# SandeepEtchASketch.net
KiCad netlist of a schematic drawn in EAGLE
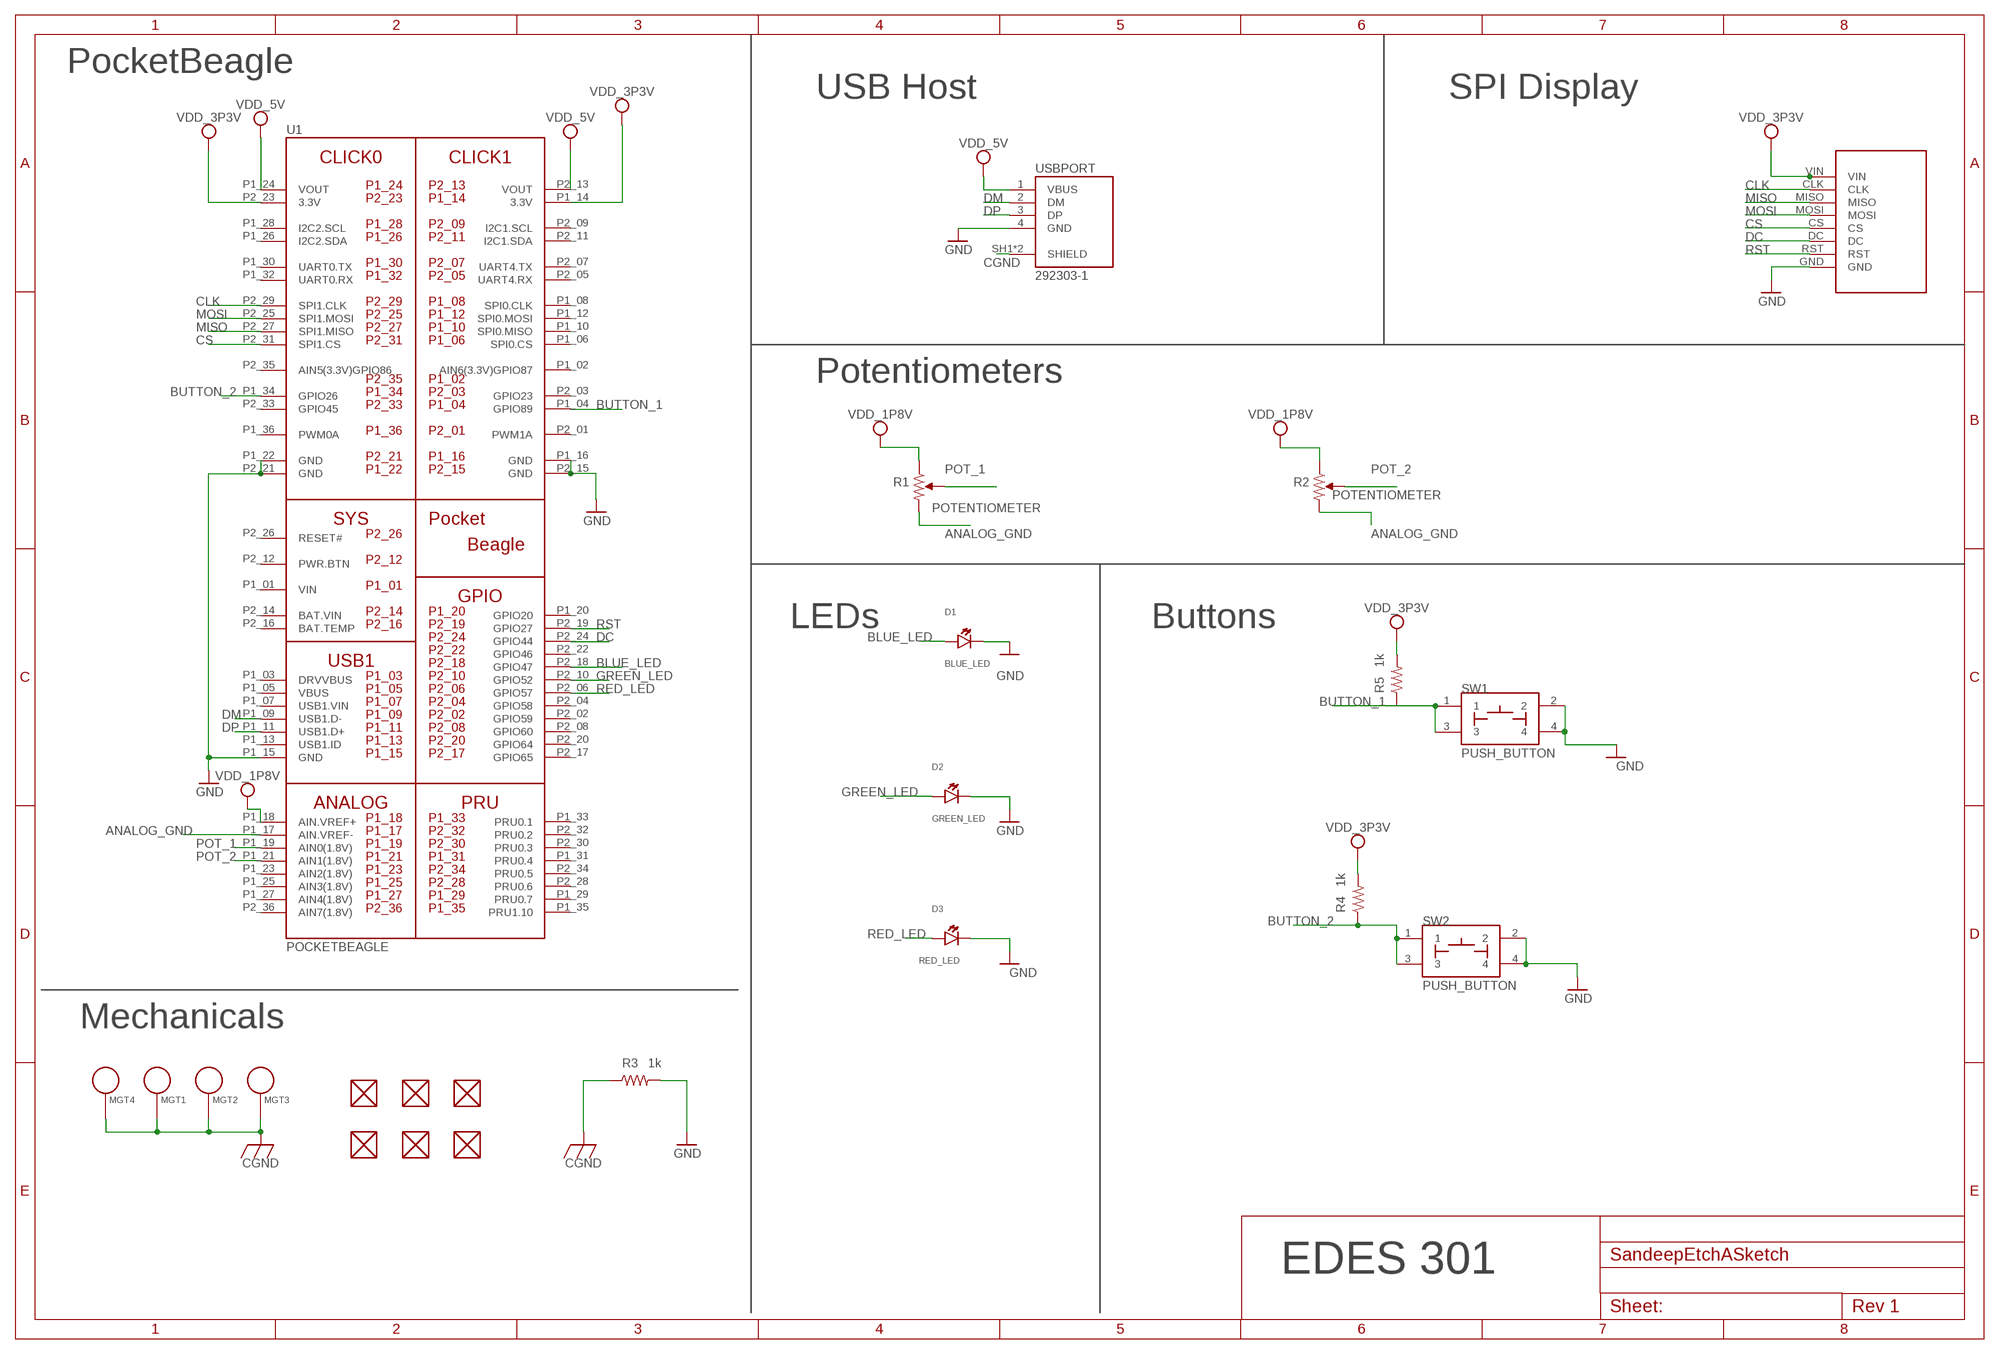
[diagram p0: schematic, sheet 1]

(export (version "E")
  (design (tool "Eeschema 10.0.6"))
  (components
    (comp (ref "D1")
      (value "BLUE_LED")
      (footprint "eagle-import:EIA-STD")
      (libsource (lib "eagle-import") (part "LED"))
    )
    (comp (ref "D2")
      (value "GREEN_LED")
      (footprint "eagle-import:EIA-STD")
      (libsource (lib "eagle-import") (part "LED"))
    )
    (comp (ref "D3")
      (value "RED_LED")
      (footprint "eagle-import:EIA-STD")
      (libsource (lib "eagle-import") (part "LED"))
    )
    (comp (ref "FUD1")
      (value "FIDUCIAL")
      (footprint "eagle-import:FIDUCIAL_40MIL")
      (libsource (lib "eagle-import") (part "FIDUCIAL"))
    )
    (comp (ref "FUD2")
      (value "FIDUCIAL")
      (footprint "eagle-import:FIDUCIAL_40MIL")
      (libsource (lib "eagle-import") (part "FIDUCIAL"))
    )
    (comp (ref "FUD3")
      (value "FIDUCIAL")
      (footprint "eagle-import:FIDUCIAL_40MIL")
      (libsource (lib "eagle-import") (part "FIDUCIAL"))
    )
    (comp (ref "FUD4")
      (value "FIDUCIAL")
      (footprint "eagle-import:FIDUCIAL_40MIL")
      (libsource (lib "eagle-import") (part "FIDUCIAL"))
    )
    (comp (ref "FUD5")
      (value "FIDUCIAL")
      (footprint "eagle-import:FIDUCIAL_40MIL")
      (libsource (lib "eagle-import") (part "FIDUCIAL"))
    )
    (comp (ref "FUD6")
      (value "FIDUCIAL")
      (footprint "eagle-import:FIDUCIAL_40MIL")
      (libsource (lib "eagle-import") (part "FIDUCIAL"))
    )
    (comp (ref "MGT1")
      (value "MOUNTING_HOLE")
      (footprint "eagle-import:MOUNTING_HOLE")
      (libsource (lib "eagle-import") (part "MOUNTING_HOLE"))
    )
    (comp (ref "MGT2")
      (value "MOUNTING_HOLE")
      (footprint "eagle-import:MOUNTING_HOLE")
      (libsource (lib "eagle-import") (part "MOUNTING_HOLE"))
    )
    (comp (ref "MGT3")
      (value "MOUNTING_HOLE")
      (footprint "eagle-import:MOUNTING_HOLE")
      (libsource (lib "eagle-import") (part "MOUNTING_HOLE"))
    )
    (comp (ref "MGT4")
      (value "MOUNTING_HOLE")
      (footprint "eagle-import:MOUNTING_HOLE")
      (libsource (lib "eagle-import") (part "MOUNTING_HOLE"))
    )
    (comp (ref "R1")
      (value "POTENTIOMETER")
      (footprint "eagle-import:POT-PO90S")
      (libsource (lib "eagle-import") (part "POTENTIOMETER"))
    )
    (comp (ref "R2")
      (value "POTENTIOMETER")
      (footprint "eagle-import:POT-PO90S")
      (libsource (lib "eagle-import") (part "POTENTIOMETER"))
    )
    (comp (ref "R3")
      (value "1k")
      (footprint "eagle-import:R0603")
      (libsource (lib "eagle-import") (part "R_R0603"))
    )
    (comp (ref "R4")
      (value "1k")
      (footprint "eagle-import:R0603")
      (libsource (lib "eagle-import") (part "R_R0603"))
    )
    (comp (ref "R5")
      (value "1k")
      (footprint "eagle-import:R0603")
      (libsource (lib "eagle-import") (part "R_R0603"))
    )
    (comp (ref "SPIDISPLAY")
      (value "SCREEN")
      (footprint "eagle-import:SCREEN")
      (libsource (lib "eagle-import") (part "SCREEN"))
    )
    (comp (ref "SW1")
      (value "PUSH_BUTTON")
      (footprint "eagle-import:BUTTON_12.5MM")
      (libsource (lib "eagle-import") (part "PUSH_BUTTON"))
    )
    (comp (ref "SW2")
      (value "PUSH_BUTTON")
      (footprint "eagle-import:BUTTON_12.5MM")
      (libsource (lib "eagle-import") (part "PUSH_BUTTON"))
    )
    (comp (ref "U1")
      (value "POCKETBEAGLE")
      (footprint "eagle-import:POCKETBEAGLE")
      (libsource (lib "eagle-import") (part "POCKETBEAGLE"))
    )
    (comp (ref "USBPORT")
      (value "292303-1")
      (footprint "eagle-import:TE_292303-1")
      (fields (field (name "MF") "TE Connectivity"))
      (libsource (lib "eagle-import") (part "292303-1"))
    )
  )
  (nets
    (net (code "1") (name "/ANALOG_GND") (class "Default")
      (node (ref "R1") (pin "CW") (pinfunction "CW_CW") (pintype "passive"))
      (node (ref "R2") (pin "CW") (pinfunction "CW_CW") (pintype "passive"))
      (node (ref "U1") (pin "P1_17") (pinfunction "AIN.VREF-_P1_17") (pintype "input"))
    )
    (net (code "2") (name "/BAT.VIN") (class "Default")
      (node (ref "U1") (pin "P2_14") (pinfunction "BAT.VIN_P2_14") (pintype "power_in"))
    )
    (net (code "3") (name "/BLUE_LED") (class "Default")
      (node (ref "D1") (pin "ANODE") (pinfunction "ANODE_ANODE") (pintype "bidirectional"))
      (node (ref "U1") (pin "P2_18") (pinfunction "GPIO47_P2_18") (pintype "bidirectional"))
    )
    (net (code "4") (name "/BUTTON_1") (class "Default")
      (node (ref "R5") (pin "1") (pinfunction "1_1") (pintype "passive"))
      (node (ref "SW1") (pin "1") (pinfunction "1_1") (pintype "bidirectional"))
      (node (ref "SW1") (pin "3") (pinfunction "3_3") (pintype "bidirectional"))
      (node (ref "U1") (pin "P1_04") (pinfunction "GPIO89_P1_04") (pintype "bidirectional"))
    )
    (net (code "5") (name "/BUTTON_2") (class "Default")
      (node (ref "R4") (pin "1") (pinfunction "1_1") (pintype "passive"))
      (node (ref "SW2") (pin "1") (pinfunction "1_1") (pintype "bidirectional"))
      (node (ref "SW2") (pin "3") (pinfunction "3_3") (pintype "bidirectional"))
      (node (ref "U1") (pin "P1_34") (pinfunction "GPIO26_P1_34") (pintype "bidirectional"))
    )
    (net (code "6") (name "/CLK") (class "Default")
      (node (ref "SPIDISPLAY") (pin "CLK") (pinfunction "CLK_CLK") (pintype "bidirectional"))
      (node (ref "U1") (pin "P2_29") (pinfunction "SPI1.CLK_P2_29") (pintype "bidirectional"))
    )
    (net (code "7") (name "/CS") (class "Default")
      (node (ref "SPIDISPLAY") (pin "CS") (pinfunction "CS_CS") (pintype "bidirectional"))
      (node (ref "U1") (pin "P2_31") (pinfunction "SPI1.CS_P2_31") (pintype "bidirectional"))
    )
    (net (code "8") (name "/DC") (class "Default")
      (node (ref "SPIDISPLAY") (pin "DC") (pinfunction "DC_DC") (pintype "bidirectional"))
      (node (ref "U1") (pin "P2_24") (pinfunction "GPIO44_P2_24") (pintype "bidirectional"))
    )
    (net (code "9") (name "/DM") (class "Default")
      (node (ref "U1") (pin "P1_09") (pinfunction "USB1.D-_P1_09") (pintype "bidirectional"))
      (node (ref "USBPORT") (pin "2") (pinfunction "DM_2") (pintype "passive"))
    )
    (net (code "10") (name "/DP") (class "Default")
      (node (ref "U1") (pin "P1_11") (pinfunction "USB1.D+_P1_11") (pintype "bidirectional"))
      (node (ref "USBPORT") (pin "3") (pinfunction "DP_3") (pintype "passive"))
    )
    (net (code "11") (name "/GREEN_LED") (class "Default")
      (node (ref "D2") (pin "ANODE") (pinfunction "ANODE_ANODE") (pintype "bidirectional"))
      (node (ref "U1") (pin "P2_10") (pinfunction "GPIO52_P2_10") (pintype "bidirectional"))
    )
    (net (code "12") (name "/MISO") (class "Default")
      (node (ref "SPIDISPLAY") (pin "MISO") (pinfunction "MISO_MISO") (pintype "bidirectional"))
      (node (ref "U1") (pin "P2_27") (pinfunction "SPI1.MISO_P2_27") (pintype "bidirectional"))
    )
    (net (code "13") (name "/MOSI") (class "Default")
      (node (ref "SPIDISPLAY") (pin "MOSI") (pinfunction "MOSI_MOSI") (pintype "bidirectional"))
      (node (ref "U1") (pin "P2_25") (pinfunction "SPI1.MOSI_P2_25") (pintype "bidirectional"))
    )
    (net (code "14") (name "/POT_1") (class "Default")
      (node (ref "R1") (pin "S") (pinfunction "S_S") (pintype "bidirectional"))
      (node (ref "U1") (pin "P1_19") (pinfunction "AIN0(1.8V)_P1_19") (pintype "input"))
    )
    (net (code "15") (name "/POT_2") (class "Default")
      (node (ref "R2") (pin "S") (pinfunction "S_S") (pintype "bidirectional"))
      (node (ref "U1") (pin "P1_21") (pinfunction "AIN1(1.8V)_P1_21") (pintype "input"))
    )
    (net (code "16") (name "/RED_LED") (class "Default")
      (node (ref "D3") (pin "ANODE") (pinfunction "ANODE_ANODE") (pintype "bidirectional"))
      (node (ref "U1") (pin "P2_06") (pinfunction "GPIO57_P2_06") (pintype "bidirectional"))
    )
    (net (code "17") (name "/RST") (class "Default")
      (node (ref "SPIDISPLAY") (pin "RST") (pinfunction "RST_RST") (pintype "bidirectional"))
      (node (ref "U1") (pin "P2_19") (pinfunction "GPIO27_P2_19") (pintype "bidirectional"))
    )
    (net (code "18") (name "/VIN") (class "Default")
      (node (ref "U1") (pin "P1_01") (pinfunction "VIN_P1_01") (pintype "power_in"))
    )
    (net (code "19") (name "CGND") (class "Default")
      (node (ref "MGT1") (pin "P$1") (pinfunction "P$1_P$1") (pintype "bidirectional"))
      (node (ref "MGT2") (pin "P$1") (pinfunction "P$1_P$1") (pintype "bidirectional"))
      (node (ref "MGT3") (pin "P$1") (pinfunction "P$1_P$1") (pintype "bidirectional"))
      (node (ref "MGT4") (pin "P$1") (pinfunction "P$1_P$1") (pintype "bidirectional"))
      (node (ref "R3") (pin "1") (pinfunction "1_1") (pintype "passive"))
      (node (ref "USBPORT") (pin "SH1") (pinfunction "SHIELD_SH1") (pintype "passive"))
      (node (ref "USBPORT") (pin "SH2") (pinfunction "SHIELD_SH2") (pintype "passive"))
    )
    (net (code "20") (name "GND") (class "Default")
      (node (ref "D1") (pin "CATHODE") (pinfunction "CATHODE_CATHODE") (pintype "bidirectional"))
      (node (ref "D2") (pin "CATHODE") (pinfunction "CATHODE_CATHODE") (pintype "bidirectional"))
      (node (ref "D3") (pin "CATHODE") (pinfunction "CATHODE_CATHODE") (pintype "bidirectional"))
      (node (ref "R3") (pin "2") (pinfunction "2_2") (pintype "passive"))
      (node (ref "SPIDISPLAY") (pin "GND") (pinfunction "GND_GND") (pintype "bidirectional"))
      (node (ref "SW1") (pin "2") (pinfunction "2_2") (pintype "bidirectional"))
      (node (ref "SW1") (pin "4") (pinfunction "4_4") (pintype "bidirectional"))
      (node (ref "SW2") (pin "2") (pinfunction "2_2") (pintype "bidirectional"))
      (node (ref "SW2") (pin "4") (pinfunction "4_4") (pintype "bidirectional"))
      (node (ref "U1") (pin "P1_15") (pinfunction "GND_P1_15") (pintype "bidirectional"))
      (node (ref "U1") (pin "P1_16") (pinfunction "GND_P1_16") (pintype "power_in"))
      (node (ref "U1") (pin "P1_22") (pinfunction "GND_P1_22") (pintype "power_in"))
      (node (ref "U1") (pin "P2_15") (pinfunction "GND_P2_15") (pintype "power_in"))
      (node (ref "U1") (pin "P2_21") (pinfunction "GND_P2_21") (pintype "power_in"))
      (node (ref "USBPORT") (pin "4") (pinfunction "GND_4") (pintype "passive"))
    )
    (net (code "21") (name "VDD_1P8V") (class "Default")
      (node (ref "R1") (pin "CCW") (pinfunction "CCW_CCW") (pintype "passive"))
      (node (ref "R2") (pin "CCW") (pinfunction "CCW_CCW") (pintype "passive"))
      (node (ref "U1") (pin "P1_18") (pinfunction "AIN.VREF+_P1_18") (pintype "input"))
    )
    (net (code "22") (name "VDD_3P3V") (class "Default")
      (node (ref "R4") (pin "2") (pinfunction "2_2") (pintype "passive"))
      (node (ref "R5") (pin "2") (pinfunction "2_2") (pintype "passive"))
      (node (ref "SPIDISPLAY") (pin "VIN") (pinfunction "VIN_VIN") (pintype "bidirectional"))
      (node (ref "U1") (pin "P1_14") (pinfunction "3.3V_P1_14") (pintype "power_in"))
      (node (ref "U1") (pin "P2_23") (pinfunction "3.3V_P2_23") (pintype "power_in"))
    )
    (net (code "23") (name "VDD_5V") (class "Default")
      (node (ref "U1") (pin "P1_24") (pinfunction "VOUT_P1_24") (pintype "power_in"))
      (node (ref "U1") (pin "P2_13") (pinfunction "VOUT_P2_13") (pintype "power_in"))
      (node (ref "USBPORT") (pin "1") (pinfunction "VBUS_1") (pintype "passive"))
    )
    (net (code "24") (name "unconnected-(FUD1-PadP$1)") (class "Default")
      (node (ref "FUD1") (pin "P$1") (pinfunction "P$1_P$1") (pintype "no_connect"))
    )
    (net (code "25") (name "unconnected-(FUD2-PadP$1)") (class "Default")
      (node (ref "FUD2") (pin "P$1") (pinfunction "P$1_P$1") (pintype "no_connect"))
    )
    (net (code "26") (name "unconnected-(FUD3-PadP$1)") (class "Default")
      (node (ref "FUD3") (pin "P$1") (pinfunction "P$1_P$1") (pintype "no_connect"))
    )
    (net (code "27") (name "unconnected-(FUD4-PadP$1)") (class "Default")
      (node (ref "FUD4") (pin "P$1") (pinfunction "P$1_P$1") (pintype "no_connect"))
    )
    (net (code "28") (name "unconnected-(FUD5-PadP$1)") (class "Default")
      (node (ref "FUD5") (pin "P$1") (pinfunction "P$1_P$1") (pintype "no_connect"))
    )
    (net (code "29") (name "unconnected-(FUD6-PadP$1)") (class "Default")
      (node (ref "FUD6") (pin "P$1") (pinfunction "P$1_P$1") (pintype "no_connect"))
    )
    (net (code "30") (name "unconnected-(U1-AIN2(1.8V)-PadP1_23)") (class "Default")
      (node (ref "U1") (pin "P1_23") (pinfunction "AIN2(1.8V)_P1_23") (pintype "input"))
    )
    (net (code "31") (name "unconnected-(U1-AIN3(1.8V)-PadP1_25)") (class "Default")
      (node (ref "U1") (pin "P1_25") (pinfunction "AIN3(1.8V)_P1_25") (pintype "input"))
    )
    (net (code "32") (name "unconnected-(U1-AIN4(1.8V)-PadP1_27)") (class "Default")
      (node (ref "U1") (pin "P1_27") (pinfunction "AIN4(1.8V)_P1_27") (pintype "input"))
    )
    (net (code "33") (name "unconnected-(U1-AIN5(3.3V)GPIO86-PadP2_35)") (class "Default")
      (node (ref "U1") (pin "P2_35") (pinfunction "AIN5(3.3V)GPIO86_P2_35") (pintype "bidirectional"))
    )
    (net (code "34") (name "unconnected-(U1-AIN6(3.3V)GPIO87-PadP1_02)") (class "Default")
      (node (ref "U1") (pin "P1_02") (pinfunction "AIN6(3.3V)GPIO87_P1_02") (pintype "bidirectional"))
    )
    (net (code "35") (name "unconnected-(U1-AIN7(1.8V)-PadP2_36)") (class "Default")
      (node (ref "U1") (pin "P2_36") (pinfunction "AIN7(1.8V)_P2_36") (pintype "input"))
    )
    (net (code "36") (name "unconnected-(U1-BAT.TEMP-PadP2_16)") (class "Default")
      (node (ref "U1") (pin "P2_16") (pinfunction "BAT.TEMP_P2_16") (pintype "input"))
    )
    (net (code "37") (name "unconnected-(U1-DRVVBUS-PadP1_03)") (class "Default")
      (node (ref "U1") (pin "P1_03") (pinfunction "DRVVBUS_P1_03") (pintype "bidirectional"))
    )
    (net (code "38") (name "unconnected-(U1-GPIO20-PadP1_20)") (class "Default")
      (node (ref "U1") (pin "P1_20") (pinfunction "GPIO20_P1_20") (pintype "bidirectional"))
    )
    (net (code "39") (name "unconnected-(U1-GPIO23-PadP2_03)") (class "Default")
      (node (ref "U1") (pin "P2_03") (pinfunction "GPIO23_P2_03") (pintype "bidirectional"))
    )
    (net (code "40") (name "unconnected-(U1-GPIO45-PadP2_33)") (class "Default")
      (node (ref "U1") (pin "P2_33") (pinfunction "GPIO45_P2_33") (pintype "bidirectional"))
    )
    (net (code "41") (name "unconnected-(U1-GPIO46-PadP2_22)") (class "Default")
      (node (ref "U1") (pin "P2_22") (pinfunction "GPIO46_P2_22") (pintype "bidirectional"))
    )
    (net (code "42") (name "unconnected-(U1-GPIO58-PadP2_04)") (class "Default")
      (node (ref "U1") (pin "P2_04") (pinfunction "GPIO58_P2_04") (pintype "bidirectional"))
    )
    (net (code "43") (name "unconnected-(U1-GPIO59-PadP2_02)") (class "Default")
      (node (ref "U1") (pin "P2_02") (pinfunction "GPIO59_P2_02") (pintype "bidirectional"))
    )
    (net (code "44") (name "unconnected-(U1-GPIO60-PadP2_08)") (class "Default")
      (node (ref "U1") (pin "P2_08") (pinfunction "GPIO60_P2_08") (pintype "bidirectional"))
    )
    (net (code "45") (name "unconnected-(U1-GPIO64-PadP2_20)") (class "Default")
      (node (ref "U1") (pin "P2_20") (pinfunction "GPIO64_P2_20") (pintype "bidirectional"))
    )
    (net (code "46") (name "unconnected-(U1-GPIO65-PadP2_17)") (class "Default")
      (node (ref "U1") (pin "P2_17") (pinfunction "GPIO65_P2_17") (pintype "bidirectional"))
    )
    (net (code "47") (name "unconnected-(U1-I2C1.SCL-PadP2_09)") (class "Default")
      (node (ref "U1") (pin "P2_09") (pinfunction "I2C1.SCL_P2_09") (pintype "bidirectional"))
    )
    (net (code "48") (name "unconnected-(U1-I2C1.SDA-PadP2_11)") (class "Default")
      (node (ref "U1") (pin "P2_11") (pinfunction "I2C1.SDA_P2_11") (pintype "bidirectional"))
    )
    (net (code "49") (name "unconnected-(U1-I2C2.SCL-PadP1_28)") (class "Default")
      (node (ref "U1") (pin "P1_28") (pinfunction "I2C2.SCL_P1_28") (pintype "bidirectional"))
    )
    (net (code "50") (name "unconnected-(U1-I2C2.SDA-PadP1_26)") (class "Default")
      (node (ref "U1") (pin "P1_26") (pinfunction "I2C2.SDA_P1_26") (pintype "bidirectional"))
    )
    (net (code "51") (name "unconnected-(U1-PRU0.1-PadP1_33)") (class "Default")
      (node (ref "U1") (pin "P1_33") (pinfunction "PRU0.1_P1_33") (pintype "bidirectional"))
    )
    (net (code "52") (name "unconnected-(U1-PRU0.2-PadP2_32)") (class "Default")
      (node (ref "U1") (pin "P2_32") (pinfunction "PRU0.2_P2_32") (pintype "bidirectional"))
    )
    (net (code "53") (name "unconnected-(U1-PRU0.3-PadP2_30)") (class "Default")
      (node (ref "U1") (pin "P2_30") (pinfunction "PRU0.3_P2_30") (pintype "bidirectional"))
    )
    (net (code "54") (name "unconnected-(U1-PRU0.4-PadP1_31)") (class "Default")
      (node (ref "U1") (pin "P1_31") (pinfunction "PRU0.4_P1_31") (pintype "bidirectional"))
    )
    (net (code "55") (name "unconnected-(U1-PRU0.5-PadP2_34)") (class "Default")
      (node (ref "U1") (pin "P2_34") (pinfunction "PRU0.5_P2_34") (pintype "bidirectional"))
    )
    (net (code "56") (name "unconnected-(U1-PRU0.6-PadP2_28)") (class "Default")
      (node (ref "U1") (pin "P2_28") (pinfunction "PRU0.6_P2_28") (pintype "bidirectional"))
    )
    (net (code "57") (name "unconnected-(U1-PRU0.7-PadP1_29)") (class "Default")
      (node (ref "U1") (pin "P1_29") (pinfunction "PRU0.7_P1_29") (pintype "bidirectional"))
    )
    (net (code "58") (name "unconnected-(U1-PRU1.10-PadP1_35)") (class "Default")
      (node (ref "U1") (pin "P1_35") (pinfunction "PRU1.10_P1_35") (pintype "bidirectional"))
    )
    (net (code "59") (name "unconnected-(U1-PWM0A-PadP1_36)") (class "Default")
      (node (ref "U1") (pin "P1_36") (pinfunction "PWM0A_P1_36") (pintype "bidirectional"))
    )
    (net (code "60") (name "unconnected-(U1-PWM1A-PadP2_01)") (class "Default")
      (node (ref "U1") (pin "P2_01") (pinfunction "PWM1A_P2_01") (pintype "bidirectional"))
    )
    (net (code "61") (name "unconnected-(U1-PWR.BTN-PadP2_12)") (class "Default")
      (node (ref "U1") (pin "P2_12") (pinfunction "PWR.BTN_P2_12") (pintype "input"))
    )
    (net (code "62") (name "unconnected-(U1-RESET#-PadP2_26)") (class "Default")
      (node (ref "U1") (pin "P2_26") (pinfunction "RESET#_P2_26") (pintype "input"))
    )
    (net (code "63") (name "unconnected-(U1-SPI0.CLK-PadP1_08)") (class "Default")
      (node (ref "U1") (pin "P1_08") (pinfunction "SPI0.CLK_P1_08") (pintype "bidirectional"))
    )
    (net (code "64") (name "unconnected-(U1-SPI0.CS-PadP1_06)") (class "Default")
      (node (ref "U1") (pin "P1_06") (pinfunction "SPI0.CS_P1_06") (pintype "bidirectional"))
    )
    (net (code "65") (name "unconnected-(U1-SPI0.MISO-PadP1_10)") (class "Default")
      (node (ref "U1") (pin "P1_10") (pinfunction "SPI0.MISO_P1_10") (pintype "bidirectional"))
    )
    (net (code "66") (name "unconnected-(U1-SPI0.MOSI-PadP1_12)") (class "Default")
      (node (ref "U1") (pin "P1_12") (pinfunction "SPI0.MOSI_P1_12") (pintype "bidirectional"))
    )
    (net (code "67") (name "unconnected-(U1-UART0.RX-PadP1_32)") (class "Default")
      (node (ref "U1") (pin "P1_32") (pinfunction "UART0.RX_P1_32") (pintype "bidirectional"))
    )
    (net (code "68") (name "unconnected-(U1-UART0.TX-PadP1_30)") (class "Default")
      (node (ref "U1") (pin "P1_30") (pinfunction "UART0.TX_P1_30") (pintype "bidirectional"))
    )
    (net (code "69") (name "unconnected-(U1-UART4.RX-PadP2_05)") (class "Default")
      (node (ref "U1") (pin "P2_05") (pinfunction "UART4.RX_P2_05") (pintype "bidirectional"))
    )
    (net (code "70") (name "unconnected-(U1-UART4.TX-PadP2_07)") (class "Default")
      (node (ref "U1") (pin "P2_07") (pinfunction "UART4.TX_P2_07") (pintype "bidirectional"))
    )
    (net (code "71") (name "unconnected-(U1-USB1.ID-PadP1_13)") (class "Default")
      (node (ref "U1") (pin "P1_13") (pinfunction "USB1.ID_P1_13") (pintype "bidirectional"))
    )
    (net (code "72") (name "unconnected-(U1-USB1.VIN-PadP1_07)") (class "Default")
      (node (ref "U1") (pin "P1_07") (pinfunction "USB1.VIN_P1_07") (pintype "bidirectional"))
    )
    (net (code "73") (name "unconnected-(U1-VBUS-PadP1_05)") (class "Default")
      (node (ref "U1") (pin "P1_05") (pinfunction "VBUS_P1_05") (pintype "bidirectional"))
    )
  )
)
